# TeleinfoMySensors.net
KiCad netlist of a schematic drawn in EAGLE
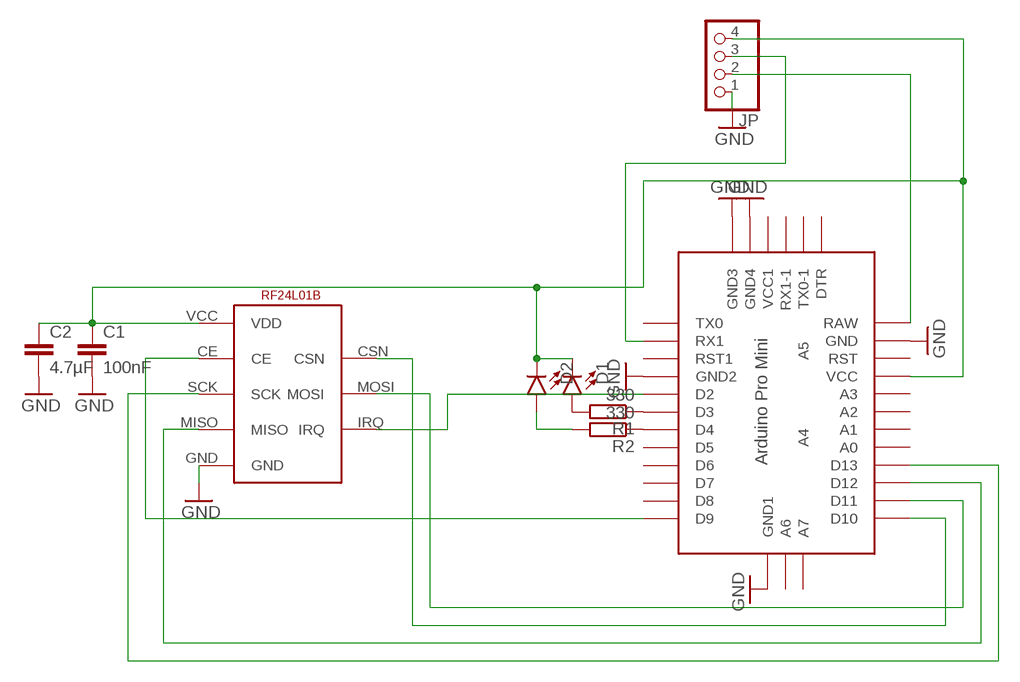
[diagram p0: schematic, sheet 1]

(export (version "E")
  (design (tool "Eeschema 10.0.6"))
  (components
    (comp (ref "C1")
      (value "100nF")
      (footprint "eagle-import:C1206")
      (libsource (lib "eagle-import") (part "C-EUC1206"))
    )
    (comp (ref "C2")
      (value "4.7µF")
      (footprint "eagle-import:C1210")
      (libsource (lib "eagle-import") (part "C-EUC1210"))
    )
    (comp (ref "D1")
      (value "LED1206")
      (footprint "eagle-import:LED-1206")
      (libsource (lib "eagle-import") (part "LED1206"))
    )
    (comp (ref "D2")
      (value "LED1206")
      (footprint "eagle-import:LED-1206")
      (libsource (lib "eagle-import") (part "LED1206"))
    )
    (comp (ref "JP")
      (value "PINHD-1X4")
      (footprint "eagle-import:1X04")
      (libsource (lib "eagle-import") (part "PINHD-1X4"))
    )
    (comp (ref "NRF")
      (value "NRF24L01BLACK")
      (footprint "eagle-import:24L01BLACK")
      (libsource (lib "eagle-import") (part "NRF24L01BLACK"))
    )
    (comp (ref "R1")
      (value "330")
      (footprint "eagle-import:M1206")
      (libsource (lib "eagle-import") (part "R-EU_M1206"))
    )
    (comp (ref "R2")
      (value "330")
      (footprint "eagle-import:M1206")
      (libsource (lib "eagle-import") (part "R-EU_M1206"))
    )
    (comp (ref "U$1")
      (value "ABK-PRO-MINI")
      (footprint "eagle-import:ABK-PRO-MINI")
      (libsource (lib "eagle-import") (part "ABK-PRO-MINI"))
    )
  )
  (nets
    (net (code "1") (name "GND") (class "Default")
      (node (ref "C1") (pin "2") (pinfunction "2_2") (pintype "passive"))
      (node (ref "C2") (pin "2") (pinfunction "2_2") (pintype "passive"))
      (node (ref "JP") (pin "1") (pinfunction "1_1") (pintype "passive"))
      (node (ref "NRF") (pin "GND") (pinfunction "GND_GND") (pintype "bidirectional"))
      (node (ref "U$1") (pin "GND") (pinfunction "GND_GND") (pintype "bidirectional"))
      (node (ref "U$1") (pin "GND1") (pinfunction "GND2_GND1") (pintype "bidirectional"))
      (node (ref "U$1") (pin "GND2") (pinfunction "GND3_GND2") (pintype "bidirectional"))
      (node (ref "U$1") (pin "GND3") (pinfunction "GND4_GND3") (pintype "bidirectional"))
      (node (ref "U$1") (pin "GND4") (pinfunction "GND1_GND4") (pintype "bidirectional"))
    )
    (net (code "2") (name "Net-(D1-PadA)") (class "Default")
      (node (ref "D1") (pin "A") (pinfunction "A_A") (pintype "passive"))
      (node (ref "R1") (pin "2") (pinfunction "2_2") (pintype "passive"))
    )
    (net (code "3") (name "Net-(D2-PadA)") (class "Default")
      (node (ref "D2") (pin "A") (pinfunction "A_A") (pintype "passive"))
      (node (ref "R2") (pin "2") (pinfunction "2_2") (pintype "passive"))
    )
    (net (code "4") (name "Net-(JP-Pad2)") (class "Default")
      (node (ref "JP") (pin "2") (pinfunction "2_2") (pintype "passive"))
      (node (ref "U$1") (pin "RAW") (pinfunction "RAW_RAW") (pintype "bidirectional"))
    )
    (net (code "5") (name "Net-(JP-Pad3)") (class "Default")
      (node (ref "JP") (pin "3") (pinfunction "3_3") (pintype "passive"))
      (node (ref "U$1") (pin "RX1") (pinfunction "RX1_RX1") (pintype "bidirectional"))
    )
    (net (code "6") (name "Net-(NRF-PadCE)") (class "Default")
      (node (ref "NRF") (pin "CE") (pinfunction "CE_CE") (pintype "bidirectional"))
      (node (ref "U$1") (pin "D9") (pinfunction "D9_D9") (pintype "bidirectional"))
    )
    (net (code "7") (name "Net-(NRF-PadCSN)") (class "Default")
      (node (ref "NRF") (pin "CSN") (pinfunction "CSN_CSN") (pintype "bidirectional"))
      (node (ref "U$1") (pin "D10") (pinfunction "D10_D10") (pintype "bidirectional"))
    )
    (net (code "8") (name "Net-(NRF-PadIRQ)") (class "Default")
      (node (ref "NRF") (pin "IRQ") (pinfunction "IRQ_IRQ") (pintype "bidirectional"))
      (node (ref "U$1") (pin "D2") (pinfunction "D2_D2") (pintype "bidirectional"))
    )
    (net (code "9") (name "Net-(NRF-PadMISO)") (class "Default")
      (node (ref "NRF") (pin "MISO") (pinfunction "MISO_MISO") (pintype "bidirectional"))
      (node (ref "U$1") (pin "D12") (pinfunction "D12_D12") (pintype "bidirectional"))
    )
    (net (code "10") (name "Net-(NRF-PadMOSI)") (class "Default")
      (node (ref "NRF") (pin "MOSI") (pinfunction "MOSI_MOSI") (pintype "bidirectional"))
      (node (ref "U$1") (pin "D11") (pinfunction "D11_D11") (pintype "bidirectional"))
    )
    (net (code "11") (name "Net-(NRF-PadSCK)") (class "Default")
      (node (ref "NRF") (pin "SCK") (pinfunction "SCK_SCK") (pintype "bidirectional"))
      (node (ref "U$1") (pin "D13") (pinfunction "D13_D13") (pintype "bidirectional"))
    )
    (net (code "12") (name "Net-(NRF-VDD)") (class "Default")
      (node (ref "C1") (pin "1") (pinfunction "1_1") (pintype "passive"))
      (node (ref "C2") (pin "1") (pinfunction "1_1") (pintype "passive"))
      (node (ref "D1") (pin "C") (pinfunction "C_C") (pintype "passive"))
      (node (ref "D2") (pin "C") (pinfunction "C_C") (pintype "passive"))
      (node (ref "JP") (pin "4") (pinfunction "4_4") (pintype "passive"))
      (node (ref "NRF") (pin "VCC") (pinfunction "VDD_VCC") (pintype "bidirectional"))
      (node (ref "U$1") (pin "VCC") (pinfunction "VCC_VCC") (pintype "bidirectional"))
    )
    (net (code "13") (name "Net-(R1-Pad1)") (class "Default")
      (node (ref "R1") (pin "1") (pinfunction "1_1") (pintype "passive"))
      (node (ref "U$1") (pin "D3") (pinfunction "D3_D3") (pintype "bidirectional"))
    )
    (net (code "14") (name "Net-(R2-Pad1)") (class "Default")
      (node (ref "R2") (pin "1") (pinfunction "1_1") (pintype "passive"))
      (node (ref "U$1") (pin "D4") (pinfunction "D4_D4") (pintype "bidirectional"))
    )
    (net (code "15") (name "unconnected-(U$1-PadA0)") (class "Default")
      (node (ref "U$1") (pin "A0") (pinfunction "A0_A0") (pintype "bidirectional"))
    )
    (net (code "16") (name "unconnected-(U$1-PadA1)") (class "Default")
      (node (ref "U$1") (pin "A1") (pinfunction "A1_A1") (pintype "bidirectional"))
    )
    (net (code "17") (name "unconnected-(U$1-PadA2)") (class "Default")
      (node (ref "U$1") (pin "A2") (pinfunction "A2_A2") (pintype "bidirectional"))
    )
    (net (code "18") (name "unconnected-(U$1-PadA3)") (class "Default")
      (node (ref "U$1") (pin "A3") (pinfunction "A3_A3") (pintype "bidirectional"))
    )
    (net (code "19") (name "unconnected-(U$1-PadA4)") (class "Default")
      (node (ref "U$1") (pin "A4") (pinfunction "A4_A4") (pintype "bidirectional"))
    )
    (net (code "20") (name "unconnected-(U$1-PadA5)") (class "Default")
      (node (ref "U$1") (pin "A5") (pinfunction "A5_A5") (pintype "bidirectional"))
    )
    (net (code "21") (name "unconnected-(U$1-PadA6)") (class "Default")
      (node (ref "U$1") (pin "A6") (pinfunction "A6_A6") (pintype "bidirectional"))
    )
    (net (code "22") (name "unconnected-(U$1-PadA7)") (class "Default")
      (node (ref "U$1") (pin "A7") (pinfunction "A7_A7") (pintype "bidirectional"))
    )
    (net (code "23") (name "unconnected-(U$1-PadD5)") (class "Default")
      (node (ref "U$1") (pin "D5") (pinfunction "D5_D5") (pintype "bidirectional"))
    )
    (net (code "24") (name "unconnected-(U$1-PadD6)") (class "Default")
      (node (ref "U$1") (pin "D6") (pinfunction "D6_D6") (pintype "bidirectional"))
    )
    (net (code "25") (name "unconnected-(U$1-PadD7)") (class "Default")
      (node (ref "U$1") (pin "D7") (pinfunction "D7_D7") (pintype "bidirectional"))
    )
    (net (code "26") (name "unconnected-(U$1-PadD8)") (class "Default")
      (node (ref "U$1") (pin "D8") (pinfunction "D8_D8") (pintype "bidirectional"))
    )
    (net (code "27") (name "unconnected-(U$1-PadDTR)") (class "Default")
      (node (ref "U$1") (pin "DTR") (pinfunction "DTR_DTR") (pintype "bidirectional"))
    )
    (net (code "28") (name "unconnected-(U$1-PadRST)") (class "Default")
      (node (ref "U$1") (pin "RST") (pinfunction "RST_RST") (pintype "bidirectional"))
    )
    (net (code "29") (name "unconnected-(U$1-PadRST1)") (class "Default")
      (node (ref "U$1") (pin "RST1") (pinfunction "RST1_RST1") (pintype "bidirectional"))
    )
    (net (code "30") (name "unconnected-(U$1-PadRX1-1)") (class "Default")
      (node (ref "U$1") (pin "RX1-1") (pinfunction "RX1-1_RX1-1") (pintype "bidirectional"))
    )
    (net (code "31") (name "unconnected-(U$1-PadTX0)") (class "Default")
      (node (ref "U$1") (pin "TX0") (pinfunction "TX0_TX0") (pintype "bidirectional"))
    )
    (net (code "32") (name "unconnected-(U$1-PadTX0-1)") (class "Default")
      (node (ref "U$1") (pin "TX0-1") (pinfunction "TX0-1_TX0-1") (pintype "bidirectional"))
    )
    (net (code "33") (name "unconnected-(U$1-PadVCC1)") (class "Default")
      (node (ref "U$1") (pin "VCC1") (pinfunction "VCC1_VCC1") (pintype "bidirectional"))
    )
  )
)
